# Power.net
KiCad netlist of a schematic drawn in Altium Designer
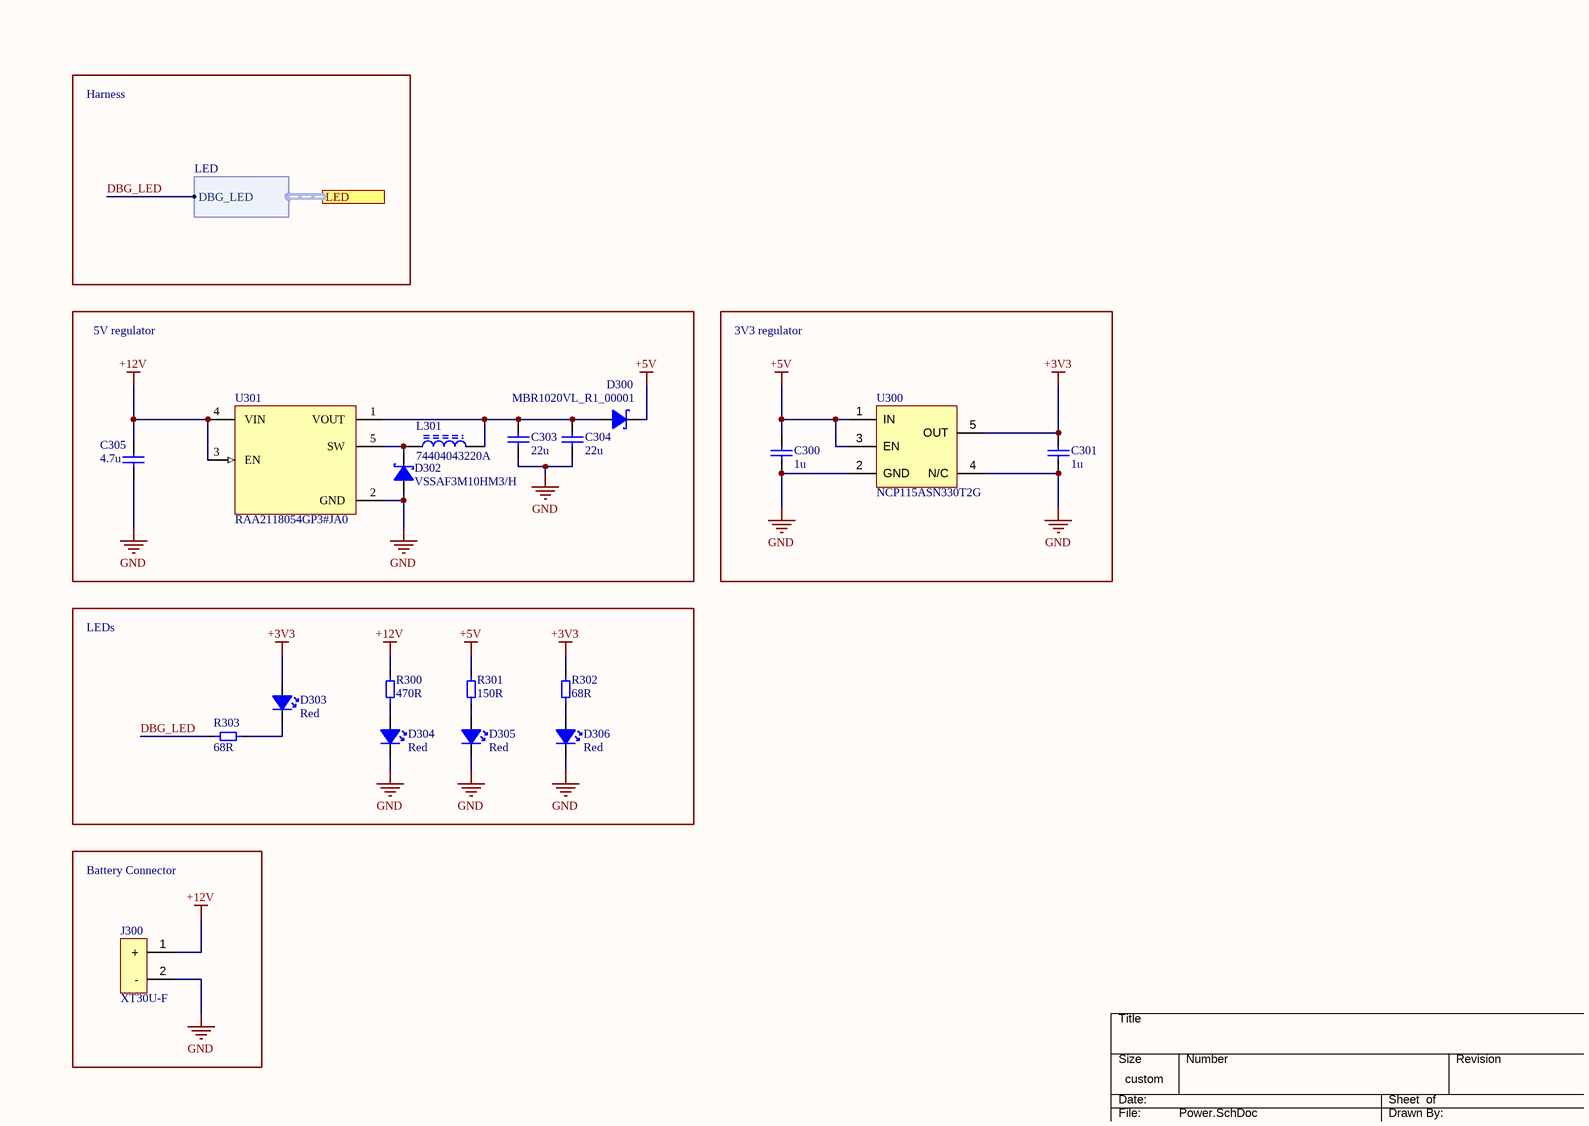
[diagram p0: Power.SchDoc]

(export (version "E")
  (design (tool "Eeschema 10.0.6"))
  (components
    (comp (ref "C300")
      (value "1u")
      (footprint "MLCC_0603_M")
      (description "MLCC, 0603, 1u, 10%, 50V, X5R")
      (fields (field (name "MANUFACTURER") "Any") (field (name "VOLTAGE") "50V"))
      (libsource (lib "Krakul Vault") (part "CAPACITOR_NONPOL_IEC"))
    )
    (comp (ref "C301")
      (value "1u")
      (footprint "MLCC_0603_M")
      (description "MLCC, 0603, 1u, 10%, 50V, X5R")
      (fields (field (name "MANUFACTURER") "Any") (field (name "VOLTAGE") "50V"))
      (libsource (lib "Krakul Vault") (part "CAPACITOR_NONPOL_IEC"))
    )
    (comp (ref "C303")
      (value "22u")
      (footprint "MLCC_0603_M")
      (description "MLCC, 0603, 22u, 10%, 16V, X5R")
      (fields (field (name "TOLERANCE") "10%") (field (name "MANUFACTURER") "Any"))
      (libsource (lib "Krakul Vault") (part "CAPACITOR_NONPOL_IEC"))
    )
    (comp (ref "C304")
      (value "22u")
      (footprint "MLCC_0603_M")
      (description "MLCC, 0603, 22u, 10%, 16V, X5R")
      (fields (field (name "TOLERANCE") "10%") (field (name "MANUFACTURER") "Any"))
      (libsource (lib "Krakul Vault") (part "CAPACITOR_NONPOL_IEC"))
    )
    (comp (ref "C305")
      (value "4.7u")
      (footprint "MLCC_1206_M")
      (description "MLCC, 1206, 4.7u, 10%, 35V, X5R")
      (fields (field (name "VOLTAGE") "35V") (field (name "TOLERANCE") "10%"))
      (libsource (lib "Krakul Vault") (part "CAPACITOR_NONPOL_IEC"))
    )
    (comp (ref "D300")
      (value "MBR1020VL_R1_00001")
      (footprint "FP-MBR1020VL_R1_00001-MFG")
      (description "Rectifier Diode, Schottky, 1 Phase, 1 Element, 1A, 20V V(RRM), Silicon")
      (fields (field (name "MANUFACTURER") "Panjit"))
      (libsource (lib "Krakul Vault") (part "Schottky generic 2 pins"))
    )
    (comp (ref "D302")
      (value "VSSAF3M10HM3/H")
      (footprint "VSSAF3M10HM3_H-Footprint-1")
      (description "Rectifier Diode, Schottky, 1 Phase, 1 Element, 2.3A, 100V V(RRM), Silicon, DO-221AC")
      (libsource (lib "Krakul Vault") (part "Schottky generic 2 pins"))
    )
    (comp (ref "D303")
      (value "Red")
      (footprint "0603 RED LED")
      (description "Generic red 0603 LED")
      (fields (field (name "PART NUMBER") "Any Red 0603 LED") (field (name "MANUFACTURER") "Any"))
      (libsource (lib "Krakul Vault") (part "LED generic"))
    )
    (comp (ref "D304")
      (value "Red")
      (footprint "0603 RED LED")
      (description "Generic red 0603 LED")
      (fields (field (name "PART NUMBER") "Any Red 0603 LED") (field (name "MANUFACTURER") "Any"))
      (libsource (lib "Krakul Vault") (part "LED generic"))
    )
    (comp (ref "D305")
      (value "Red")
      (footprint "0603 RED LED")
      (description "Generic red 0603 LED")
      (fields (field (name "PART NUMBER") "Any Red 0603 LED") (field (name "MANUFACTURER") "Any"))
      (libsource (lib "Krakul Vault") (part "LED generic"))
    )
    (comp (ref "D306")
      (value "Red")
      (footprint "0603 RED LED")
      (description "Generic red 0603 LED")
      (fields (field (name "PART NUMBER") "Any Red 0603 LED") (field (name "MANUFACTURER") "Any"))
      (libsource (lib "Krakul Vault") (part "LED generic"))
    )
    (comp (ref "J300")
      (value "XT30U-F")
      (footprint "XT30U-F")
      (description "Power Connector")
      (fields (field (name "MANUFACTURER") "AMASS"))
      (libsource (lib "Krakul Vault") (part "XT30U-F-Symbol-1"))
    )
    (comp (ref "L301")
      (value "74404043220A")
      (footprint "WE-LQS_4025")
      (description "General Purpose Inductor, 22uH, 20%, 1 Element, Nickel-zinc Ferrite-Core, SMD, 1616")
      (fields (field (name "MANUFACTURER") "Wurth Elektronik"))
      (libsource (lib "Krakul Vault") (part "INDUCTOR_SHIELDED"))
    )
    (comp (ref "R300")
      (value "470R")
      (footprint "Resistor_0603_M")
      (description "Resistor, 0603, 680R, 1%, 1/10W")
      (fields (field (name "POWER") "100mW") (field (name "TOLERANCE") "1%"))
      (libsource (lib "Krakul Vault") (part "RESISTOR_GENERIC_IEC"))
    )
    (comp (ref "R301")
      (value "150R")
      (footprint "Resistor_0603_M")
      (description "Resistor, 0603, 200R, 1%, 1/10W")
      (fields (field (name "TOLERANCE") "1%") (field (name "POWER") "100mW"))
      (libsource (lib "Krakul Vault") (part "RESISTOR_GENERIC_IEC"))
    )
    (comp (ref "R302")
      (value "68R")
      (footprint "Resistor_0603_M")
      (description "Resistor, 0603, 100R, ≤5%, ≥1/16W")
      (fields (field (name "MANUFACTURER") "Any"))
      (libsource (lib "Krakul Vault") (part "RESISTOR_GENERIC_IEC"))
    )
    (comp (ref "R303")
      (value "68R")
      (footprint "Resistor_0603_M")
      (description "Resistor, 0603, 200R, 1%, 1/10W")
      (fields (field (name "TOLERANCE") "1%") (field (name "POWER") "100mW"))
      (libsource (lib "Krakul Vault") (part "RESISTOR_GENERIC_IEC"))
    )
    (comp (ref "U300")
      (value "NCP115ASN330T2G")
      (footprint "TSOP-5")
      (fields (field (name "MANUFACTURER") "onsemi"))
      (libsource (lib "Krakul Vault") (part "NCP115ASN330T2G"))
    )
    (comp (ref "U301")
      (value "RAA2118054GP3#JA0")
      (footprint "P5_064B_MFG")
      (description "Switching Regulator, Current-mode, 0.3A, 230kHz Switching Freq-Max, PDSO5")
      (fields (field (name "MANUFACTURER") "Renesas / Intersil"))
      (libsource (lib "Krakul Vault") (part "04ef17e7ed04f306c00cc4b237f44d7"))
    )
  )
  (nets
    (net (code "2") (name "+3V3") (class "Default")
      (node (ref "C301") (pin "2") (pinfunction "2_2") (pintype "passive"))
      (node (ref "D303") (pin "2") (pinfunction "A_2") (pintype "passive"))
      (node (ref "R302") (pin "2") (pinfunction "2_2") (pintype "passive"))
      (node (ref "U300") (pin "5") (pinfunction "OUT_5") (pintype "passive"))
    )
    (net (code "3") (name "+5V") (class "Default")
      (node (ref "C300") (pin "2") (pinfunction "2_2") (pintype "passive"))
      (node (ref "D300") (pin "1") (pinfunction "C_1") (pintype "passive"))
      (node (ref "R301") (pin "1") (pinfunction "1_1") (pintype "passive"))
      (node (ref "U300") (pin "1") (pinfunction "IN_1") (pintype "passive"))
      (node (ref "U300") (pin "3") (pinfunction "EN_3") (pintype "passive"))
    )
    (net (code "4") (name "+12V") (class "Default")
      (node (ref "C305") (pin "2") (pinfunction "2_2") (pintype "passive"))
      (node (ref "J300") (pin "1") (pinfunction "+_1") (pintype "passive"))
      (node (ref "R300") (pin "2") (pinfunction "2_2") (pintype "passive"))
      (node (ref "U301") (pin "3") (pinfunction "EN_3") (pintype "input"))
      (node (ref "U301") (pin "4") (pinfunction "VIN_4") (pintype "power_in"))
    )
    (net (code "5") (name "/DBG_LED") (class "Default")
      (node (ref "R303") (pin "2") (pinfunction "2_2") (pintype "passive"))
    )
    (net (code "7") (name "GND") (class "Default")
      (node (ref "C300") (pin "1") (pinfunction "1_1") (pintype "passive"))
      (node (ref "C301") (pin "1") (pinfunction "1_1") (pintype "passive"))
      (node (ref "C303") (pin "1") (pinfunction "1_1") (pintype "passive"))
      (node (ref "C304") (pin "1") (pinfunction "1_1") (pintype "passive"))
      (node (ref "C305") (pin "1") (pinfunction "1_1") (pintype "passive"))
      (node (ref "D302") (pin "2") (pinfunction "A_2") (pintype "passive"))
      (node (ref "D304") (pin "1") (pinfunction "C_1") (pintype "passive"))
      (node (ref "D305") (pin "1") (pinfunction "C_1") (pintype "passive"))
      (node (ref "D306") (pin "1") (pinfunction "C_1") (pintype "passive"))
      (node (ref "J300") (pin "2") (pinfunction "-_2") (pintype "passive"))
      (node (ref "U300") (pin "2") (pinfunction "GND_2") (pintype "passive"))
      (node (ref "U300") (pin "4") (pinfunction "N/C_4") (pintype "passive"))
      (node (ref "U301") (pin "2") (pinfunction "GND_2") (pintype "power_in"))
    )
    (net (code "8") (name "Net-(D300-A)") (class "Default")
      (node (ref "C303") (pin "2") (pinfunction "2_2") (pintype "passive"))
      (node (ref "C304") (pin "2") (pinfunction "2_2") (pintype "passive"))
      (node (ref "D300") (pin "2") (pinfunction "A_2") (pintype "passive"))
      (node (ref "L301") (pin "2") (pinfunction "2_2") (pintype "passive"))
      (node (ref "U301") (pin "1") (pinfunction "VOUT_1") (pintype "power_in"))
    )
    (net (code "9") (name "Net-(D302-C)") (class "Default")
      (node (ref "D302") (pin "1") (pinfunction "C_1") (pintype "passive"))
      (node (ref "L301") (pin "1") (pinfunction "1_1") (pintype "passive"))
      (node (ref "U301") (pin "5") (pinfunction "SW_5") (pintype "passive"))
    )
    (net (code "10") (name "Net-(D303-C)") (class "Default")
      (node (ref "D303") (pin "1") (pinfunction "C_1") (pintype "passive"))
      (node (ref "R303") (pin "1") (pinfunction "1_1") (pintype "passive"))
    )
    (net (code "11") (name "Net-(D304-A)") (class "Default")
      (node (ref "D304") (pin "2") (pinfunction "A_2") (pintype "passive"))
      (node (ref "R300") (pin "1") (pinfunction "1_1") (pintype "passive"))
    )
    (net (code "12") (name "Net-(D305-A)") (class "Default")
      (node (ref "D305") (pin "2") (pinfunction "A_2") (pintype "passive"))
      (node (ref "R301") (pin "2") (pinfunction "2_2") (pintype "passive"))
    )
    (net (code "13") (name "Net-(D306-A)") (class "Default")
      (node (ref "D306") (pin "2") (pinfunction "A_2") (pintype "passive"))
      (node (ref "R302") (pin "1") (pinfunction "1_1") (pintype "passive"))
    )
  )
)
